# iBuff_Gimp.net
KiCad netlist of a schematic drawn in EAGLE
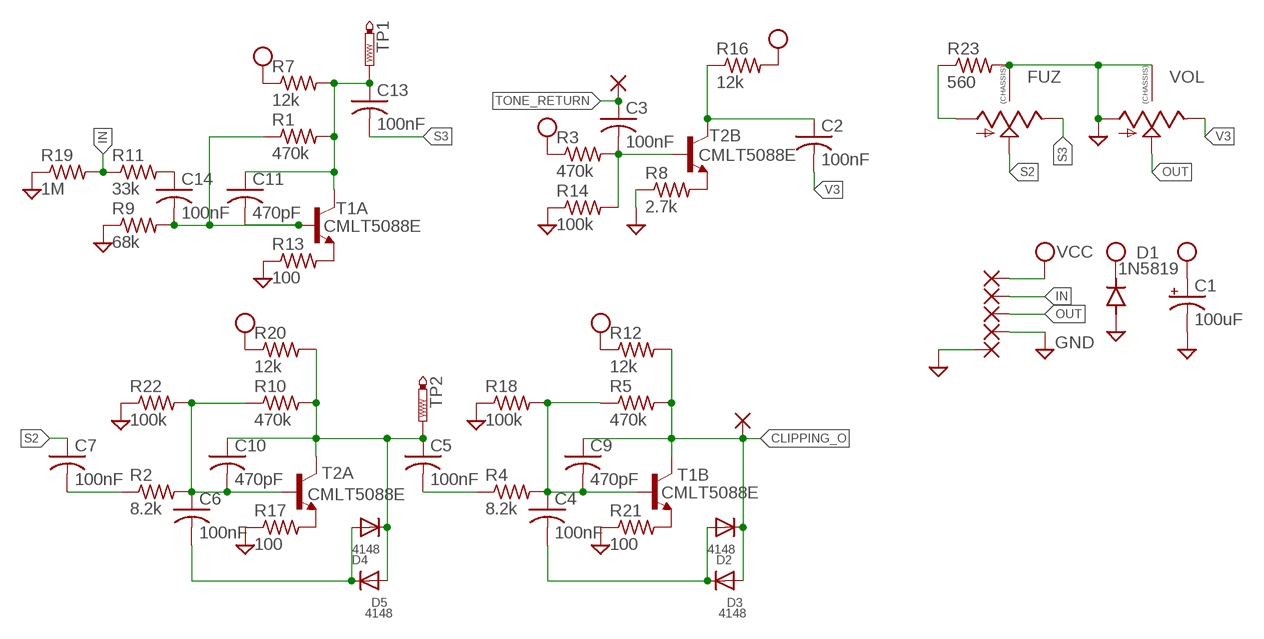
[diagram p0: schematic, sheet 1]

(export (version "E")
  (design (tool "Eeschema 10.0.6"))
  (components
    (comp (ref "C1")
      (value "100uF")
      (footprint "eagle-import:CPOL-RADIAL-2.5MM-6.5MM")
      (libsource (lib "eagle-import") (part "100UF-POLAR-RADIAL-2.5MM-25V-20%"))
    )
    (comp (ref "C2")
      (value "100nF")
      (footprint "eagle-import:C0603")
      (libsource (lib "eagle-import") (part "C-USC0603"))
    )
    (comp (ref "C3")
      (value "100nF")
      (footprint "eagle-import:C0603")
      (libsource (lib "eagle-import") (part "C-USC0603"))
    )
    (comp (ref "C4")
      (value "100nF")
      (footprint "eagle-import:C0603")
      (libsource (lib "eagle-import") (part "C-USC0603"))
    )
    (comp (ref "C5")
      (value "100nF")
      (footprint "eagle-import:C0603")
      (libsource (lib "eagle-import") (part "C-USC0603"))
    )
    (comp (ref "C6")
      (value "100nF")
      (footprint "eagle-import:C0603")
      (libsource (lib "eagle-import") (part "C-USC0603"))
    )
    (comp (ref "C7")
      (value "100nF")
      (footprint "eagle-import:C0603")
      (libsource (lib "eagle-import") (part "C-USC0603"))
    )
    (comp (ref "C9")
      (value "470pF")
      (footprint "eagle-import:C0603")
      (libsource (lib "eagle-import") (part "C-USC0603"))
    )
    (comp (ref "C10")
      (value "470pF")
      (footprint "eagle-import:C0603")
      (libsource (lib "eagle-import") (part "C-USC0603"))
    )
    (comp (ref "C11")
      (value "470pF")
      (footprint "eagle-import:C0603")
      (libsource (lib "eagle-import") (part "C-USC0603"))
    )
    (comp (ref "C13")
      (value "100nF")
      (footprint "eagle-import:C0603")
      (libsource (lib "eagle-import") (part "C-USC0603"))
    )
    (comp (ref "C14")
      (value "100nF")
      (footprint "eagle-import:C0603")
      (libsource (lib "eagle-import") (part "C-USC0603"))
    )
    (comp (ref "D1")
      (value "1N5819")
      (footprint "eagle-import:SOD123")
      (libsource (lib "eagle-import") (part "DIODE-SOD123"))
    )
    (comp (ref "D2")
      (value "4148")
      (footprint "eagle-import:SOD-123")
      (libsource (lib "eagle-import") (part "DIODESOD-123"))
    )
    (comp (ref "D3")
      (value "4148")
      (footprint "eagle-import:SOD-123")
      (libsource (lib "eagle-import") (part "DIODESOD-123"))
    )
    (comp (ref "D4")
      (value "4148")
      (footprint "eagle-import:SOD-123")
      (libsource (lib "eagle-import") (part "DIODESOD-123"))
    )
    (comp (ref "D5")
      (value "4148")
      (footprint "eagle-import:SOD-123")
      (libsource (lib "eagle-import") (part "DIODESOD-123"))
    )
    (comp (ref "FUZ")
      (value "9MM_SNAP-IN_POT_CHASSIS")
      (footprint "eagle-import:9MM_SNAP-IN_POT")
      (libsource (lib "eagle-import") (part "9MM_SNAP-IN_POT_CHASSIS"))
    )
    (comp (ref "PAD1")
      (value "1,6/0,8")
      (footprint "eagle-import:1,6_0,8")
      (libsource (lib "eagle-import") (part "1,6/0,8"))
    )
    (comp (ref "PAD2")
      (value "1,6/0,8")
      (footprint "eagle-import:1,6_0,8")
      (libsource (lib "eagle-import") (part "1,6/0,8"))
    )
    (comp (ref "PAD3")
      (value "1,6/0,8")
      (footprint "eagle-import:1,6_0,8")
      (libsource (lib "eagle-import") (part "1,6/0,8"))
    )
    (comp (ref "PAD4")
      (value "1,6/0,8")
      (footprint "eagle-import:1,6_0,8")
      (libsource (lib "eagle-import") (part "1,6/0,8"))
    )
    (comp (ref "PAD5")
      (value "1,6/0,8")
      (footprint "eagle-import:1,6_0,8")
      (libsource (lib "eagle-import") (part "1,6/0,8"))
    )
    (comp (ref "PAD6")
      (value "1,6/0,8")
      (footprint "eagle-import:1,6_0,8")
      (libsource (lib "eagle-import") (part "1,6/0,8"))
    )
    (comp (ref "PAD7")
      (value "1,6/0,8")
      (footprint "eagle-import:1,6_0,8")
      (libsource (lib "eagle-import") (part "1,6/0,8"))
    )
    (comp (ref "R1")
      (value "470k")
      (footprint "eagle-import:R0603")
      (libsource (lib "eagle-import") (part "R-US_R0603"))
    )
    (comp (ref "R2")
      (value "8.2k")
      (footprint "eagle-import:R0603")
      (libsource (lib "eagle-import") (part "R-US_R0603"))
    )
    (comp (ref "R3")
      (value "470k")
      (footprint "eagle-import:R0603")
      (libsource (lib "eagle-import") (part "R-US_R0603"))
    )
    (comp (ref "R4")
      (value "8.2k")
      (footprint "eagle-import:R0603")
      (libsource (lib "eagle-import") (part "R-US_R0603"))
    )
    (comp (ref "R5")
      (value "470k")
      (footprint "eagle-import:R0603")
      (libsource (lib "eagle-import") (part "R-US_R0603"))
    )
    (comp (ref "R7")
      (value "12k")
      (footprint "eagle-import:R0603")
      (libsource (lib "eagle-import") (part "R-US_R0603"))
    )
    (comp (ref "R8")
      (value "2.7k")
      (footprint "eagle-import:R0603")
      (libsource (lib "eagle-import") (part "R-US_R0603"))
    )
    (comp (ref "R9")
      (value "68k")
      (footprint "eagle-import:R0603")
      (libsource (lib "eagle-import") (part "R-US_R0603"))
    )
    (comp (ref "R10")
      (value "470k")
      (footprint "eagle-import:R0603")
      (libsource (lib "eagle-import") (part "R-US_R0603"))
    )
    (comp (ref "R11")
      (value "33k")
      (footprint "eagle-import:R0603")
      (libsource (lib "eagle-import") (part "R-US_R0603"))
    )
    (comp (ref "R12")
      (value "12k")
      (footprint "eagle-import:R0603")
      (libsource (lib "eagle-import") (part "R-US_R0603"))
    )
    (comp (ref "R13")
      (value "100")
      (footprint "eagle-import:R0603")
      (libsource (lib "eagle-import") (part "R-US_R0603"))
    )
    (comp (ref "R14")
      (value "100k")
      (footprint "eagle-import:R0603")
      (libsource (lib "eagle-import") (part "R-US_R0603"))
    )
    (comp (ref "R16")
      (value "12k")
      (footprint "eagle-import:R0603")
      (libsource (lib "eagle-import") (part "R-US_R0603"))
    )
    (comp (ref "R17")
      (value "100")
      (footprint "eagle-import:R0603")
      (libsource (lib "eagle-import") (part "R-US_R0603"))
    )
    (comp (ref "R18")
      (value "100k")
      (footprint "eagle-import:R0603")
      (libsource (lib "eagle-import") (part "R-US_R0603"))
    )
    (comp (ref "R19")
      (value "1M")
      (footprint "eagle-import:R0603")
      (libsource (lib "eagle-import") (part "R-US_R0603"))
    )
    (comp (ref "R20")
      (value "12k")
      (footprint "eagle-import:R0603")
      (libsource (lib "eagle-import") (part "R-US_R0603"))
    )
    (comp (ref "R21")
      (value "100")
      (footprint "eagle-import:R0603")
      (libsource (lib "eagle-import") (part "R-US_R0603"))
    )
    (comp (ref "R22")
      (value "100k")
      (footprint "eagle-import:R0603")
      (libsource (lib "eagle-import") (part "R-US_R0603"))
    )
    (comp (ref "R23")
      (value "560")
      (footprint "eagle-import:R0603")
      (libsource (lib "eagle-import") (part "R-US_R0603"))
    )
    (comp (ref "T1")
      (value "CMLT5088E")
      (footprint "eagle-import:SOT563")
      (libsource (lib "eagle-import") (part "CMLT5088E"))
    )
    (comp (ref "T2")
      (value "CMLT5088E")
      (footprint "eagle-import:SOT563")
      (libsource (lib "eagle-import") (part "CMLT5088E"))
    )
    (comp (ref "TP1")
      (value "PTR1TP08R")
      (footprint "eagle-import:TP08R")
      (libsource (lib "eagle-import") (part "PTR1TP08R"))
    )
    (comp (ref "TP2")
      (value "PTR1TP08R")
      (footprint "eagle-import:TP08R")
      (libsource (lib "eagle-import") (part "PTR1TP08R"))
    )
    (comp (ref "VOL")
      (value "9MM_SNAP-IN_POT_CHASSIS")
      (footprint "eagle-import:9MM_SNAP-IN_POT")
      (libsource (lib "eagle-import") (part "9MM_SNAP-IN_POT_CHASSIS"))
    )
  )
  (nets
    (net (code "1") (name "CLIPPING_O") (class "Default")
      (node (ref "C9") (pin "1") (pinfunction "1_1") (pintype "passive"))
      (node (ref "D2") (pin "C") (pinfunction "C_C") (pintype "passive"))
      (node (ref "D3") (pin "A") (pinfunction "A_A") (pintype "passive"))
      (node (ref "PAD5") (pin "1") (pinfunction "P_1") (pintype "passive"))
      (node (ref "R12") (pin "2") (pinfunction "2_2") (pintype "passive"))
      (node (ref "R5") (pin "2") (pinfunction "2_2") (pintype "passive"))
      (node (ref "T1") (pin "3") (pinfunction "C_3") (pintype "passive"))
    )
    (net (code "2") (name "GND") (class "Default")
      (node (ref "C1") (pin "2") (pinfunction "-_2") (pintype "passive"))
      (node (ref "D1") (pin "A") (pinfunction "A_A") (pintype "passive"))
      (node (ref "FUZ") (pin "CHASSIS1") (pinfunction "P$1_CHASSIS1") (pintype "passive"))
      (node (ref "FUZ") (pin "CHASSIS2") (pinfunction "P$1_CHASSIS2") (pintype "passive"))
      (node (ref "PAD4") (pin "1") (pinfunction "P_1") (pintype "passive"))
      (node (ref "PAD7") (pin "1") (pinfunction "P_1") (pintype "passive"))
      (node (ref "R13") (pin "1") (pinfunction "1_1") (pintype "passive"))
      (node (ref "R14") (pin "1") (pinfunction "1_1") (pintype "passive"))
      (node (ref "R17") (pin "1") (pinfunction "1_1") (pintype "passive"))
      (node (ref "R18") (pin "1") (pinfunction "1_1") (pintype "passive"))
      (node (ref "R19") (pin "1") (pinfunction "1_1") (pintype "passive"))
      (node (ref "R21") (pin "1") (pinfunction "1_1") (pintype "passive"))
      (node (ref "R22") (pin "1") (pinfunction "1_1") (pintype "passive"))
      (node (ref "R23") (pin "2") (pinfunction "2_2") (pintype "passive"))
      (node (ref "R8") (pin "1") (pinfunction "1_1") (pintype "passive"))
      (node (ref "R9") (pin "1") (pinfunction "1_1") (pintype "passive"))
      (node (ref "VOL") (pin "1") (pinfunction "A_1") (pintype "passive"))
      (node (ref "VOL") (pin "CHASSIS1") (pinfunction "P$1_CHASSIS1") (pintype "passive"))
      (node (ref "VOL") (pin "CHASSIS2") (pinfunction "P$1_CHASSIS2") (pintype "passive"))
    )
    (net (code "3") (name "IN") (class "Default")
      (node (ref "PAD2") (pin "1") (pinfunction "P_1") (pintype "passive"))
      (node (ref "R11") (pin "1") (pinfunction "1_1") (pintype "passive"))
      (node (ref "R19") (pin "2") (pinfunction "2_2") (pintype "passive"))
    )
    (net (code "4") (name "Net-(C4-Pad2)") (class "Default")
      (node (ref "C4") (pin "2") (pinfunction "2_2") (pintype "passive"))
      (node (ref "D2") (pin "A") (pinfunction "A_A") (pintype "passive"))
      (node (ref "D3") (pin "C") (pinfunction "C_C") (pintype "passive"))
    )
    (net (code "5") (name "Net-(C5-Pad2)") (class "Default")
      (node (ref "C5") (pin "2") (pinfunction "2_2") (pintype "passive"))
      (node (ref "R4") (pin "1") (pinfunction "1_1") (pintype "passive"))
    )
    (net (code "6") (name "Net-(C6-Pad2)") (class "Default")
      (node (ref "C6") (pin "2") (pinfunction "2_2") (pintype "passive"))
      (node (ref "D4") (pin "A") (pinfunction "A_A") (pintype "passive"))
      (node (ref "D5") (pin "C") (pinfunction "C_C") (pintype "passive"))
    )
    (net (code "7") (name "Net-(C7-Pad2)") (class "Default")
      (node (ref "C7") (pin "2") (pinfunction "2_2") (pintype "passive"))
      (node (ref "R2") (pin "1") (pinfunction "1_1") (pintype "passive"))
    )
    (net (code "8") (name "Net-(C14-Pad1)") (class "Default")
      (node (ref "C14") (pin "1") (pinfunction "1_1") (pintype "passive"))
      (node (ref "R11") (pin "2") (pinfunction "2_2") (pintype "passive"))
    )
    (net (code "9") (name "Net-(FUZ-A)") (class "Default")
      (node (ref "FUZ") (pin "1") (pinfunction "A_1") (pintype "passive"))
      (node (ref "R23") (pin "1") (pinfunction "1_1") (pintype "passive"))
    )
    (net (code "10") (name "Net-(T1A-B)") (class "Default")
      (node (ref "C11") (pin "2") (pinfunction "2_2") (pintype "passive"))
      (node (ref "C14") (pin "2") (pinfunction "2_2") (pintype "passive"))
      (node (ref "R1") (pin "1") (pinfunction "1_1") (pintype "passive"))
      (node (ref "R9") (pin "2") (pinfunction "2_2") (pintype "passive"))
      (node (ref "T1") (pin "2") (pinfunction "B_2") (pintype "passive"))
    )
    (net (code "11") (name "Net-(T1A-C)") (class "Default")
      (node (ref "C11") (pin "1") (pinfunction "1_1") (pintype "passive"))
      (node (ref "C13") (pin "1") (pinfunction "1_1") (pintype "passive"))
      (node (ref "R1") (pin "2") (pinfunction "2_2") (pintype "passive"))
      (node (ref "R7") (pin "2") (pinfunction "2_2") (pintype "passive"))
      (node (ref "T1") (pin "6") (pinfunction "C_6") (pintype "passive"))
      (node (ref "TP1") (pin "TP") (pinfunction "TP_TP") (pintype "input"))
    )
    (net (code "12") (name "Net-(T1A-E)") (class "Default")
      (node (ref "R13") (pin "2") (pinfunction "2_2") (pintype "passive"))
      (node (ref "T1") (pin "1") (pinfunction "E_1") (pintype "passive"))
    )
    (net (code "13") (name "Net-(T1B-B)") (class "Default")
      (node (ref "C4") (pin "1") (pinfunction "1_1") (pintype "passive"))
      (node (ref "C9") (pin "2") (pinfunction "2_2") (pintype "passive"))
      (node (ref "R18") (pin "2") (pinfunction "2_2") (pintype "passive"))
      (node (ref "R4") (pin "2") (pinfunction "2_2") (pintype "passive"))
      (node (ref "R5") (pin "1") (pinfunction "1_1") (pintype "passive"))
      (node (ref "T1") (pin "5") (pinfunction "B_5") (pintype "passive"))
    )
    (net (code "14") (name "Net-(T1B-E)") (class "Default")
      (node (ref "R21") (pin "2") (pinfunction "2_2") (pintype "passive"))
      (node (ref "T1") (pin "4") (pinfunction "E_4") (pintype "passive"))
    )
    (net (code "15") (name "Net-(T2A-B)") (class "Default")
      (node (ref "C10") (pin "2") (pinfunction "2_2") (pintype "passive"))
      (node (ref "C6") (pin "1") (pinfunction "1_1") (pintype "passive"))
      (node (ref "R10") (pin "1") (pinfunction "1_1") (pintype "passive"))
      (node (ref "R2") (pin "2") (pinfunction "2_2") (pintype "passive"))
      (node (ref "R22") (pin "2") (pinfunction "2_2") (pintype "passive"))
      (node (ref "T2") (pin "2") (pinfunction "B_2") (pintype "passive"))
    )
    (net (code "16") (name "Net-(T2A-C)") (class "Default")
      (node (ref "C10") (pin "1") (pinfunction "1_1") (pintype "passive"))
      (node (ref "C5") (pin "1") (pinfunction "1_1") (pintype "passive"))
      (node (ref "D4") (pin "C") (pinfunction "C_C") (pintype "passive"))
      (node (ref "D5") (pin "A") (pinfunction "A_A") (pintype "passive"))
      (node (ref "R10") (pin "2") (pinfunction "2_2") (pintype "passive"))
      (node (ref "R20") (pin "2") (pinfunction "2_2") (pintype "passive"))
      (node (ref "T2") (pin "6") (pinfunction "C_6") (pintype "passive"))
      (node (ref "TP2") (pin "TP") (pinfunction "TP_TP") (pintype "input"))
    )
    (net (code "17") (name "Net-(T2A-E)") (class "Default")
      (node (ref "R17") (pin "2") (pinfunction "2_2") (pintype "passive"))
      (node (ref "T2") (pin "1") (pinfunction "E_1") (pintype "passive"))
    )
    (net (code "18") (name "Net-(T2B-B)") (class "Default")
      (node (ref "C3") (pin "2") (pinfunction "2_2") (pintype "passive"))
      (node (ref "R14") (pin "2") (pinfunction "2_2") (pintype "passive"))
      (node (ref "R3") (pin "2") (pinfunction "2_2") (pintype "passive"))
      (node (ref "T2") (pin "5") (pinfunction "B_5") (pintype "passive"))
    )
    (net (code "19") (name "Net-(T2B-C)") (class "Default")
      (node (ref "C2") (pin "1") (pinfunction "1_1") (pintype "passive"))
      (node (ref "R16") (pin "1") (pinfunction "1_1") (pintype "passive"))
      (node (ref "T2") (pin "3") (pinfunction "C_3") (pintype "passive"))
    )
    (net (code "20") (name "Net-(T2B-E)") (class "Default")
      (node (ref "R8") (pin "2") (pinfunction "2_2") (pintype "passive"))
      (node (ref "T2") (pin "4") (pinfunction "E_4") (pintype "passive"))
    )
    (net (code "21") (name "OUT") (class "Default")
      (node (ref "PAD3") (pin "1") (pinfunction "P_1") (pintype "passive"))
      (node (ref "VOL") (pin "2") (pinfunction "S_2") (pintype "passive"))
    )
    (net (code "22") (name "S2") (class "Default")
      (node (ref "C7") (pin "1") (pinfunction "1_1") (pintype "passive"))
      (node (ref "FUZ") (pin "2") (pinfunction "S_2") (pintype "passive"))
    )
    (net (code "23") (name "S3") (class "Default")
      (node (ref "C13") (pin "2") (pinfunction "2_2") (pintype "passive"))
      (node (ref "FUZ") (pin "3") (pinfunction "E_3") (pintype "passive"))
    )
    (net (code "24") (name "TONE_RETURN") (class "Default")
      (node (ref "C3") (pin "1") (pinfunction "1_1") (pintype "passive"))
      (node (ref "PAD6") (pin "1") (pinfunction "P_1") (pintype "passive"))
    )
    (net (code "25") (name "V3") (class "Default")
      (node (ref "C2") (pin "2") (pinfunction "2_2") (pintype "passive"))
      (node (ref "VOL") (pin "3") (pinfunction "E_3") (pintype "passive"))
    )
    (net (code "26") (name "VCC") (class "Default")
      (node (ref "C1") (pin "1") (pinfunction "+_1") (pintype "passive"))
      (node (ref "D1") (pin "C") (pinfunction "C_C") (pintype "passive"))
      (node (ref "PAD1") (pin "1") (pinfunction "P_1") (pintype "passive"))
      (node (ref "R12") (pin "1") (pinfunction "1_1") (pintype "passive"))
      (node (ref "R16") (pin "2") (pinfunction "2_2") (pintype "passive"))
      (node (ref "R20") (pin "1") (pinfunction "1_1") (pintype "passive"))
      (node (ref "R3") (pin "1") (pinfunction "1_1") (pintype "passive"))
      (node (ref "R7") (pin "1") (pinfunction "1_1") (pintype "passive"))
    )
  )
)
